# 003_Connectors.net
KiCad netlist of a schematic drawn in Altium Designer
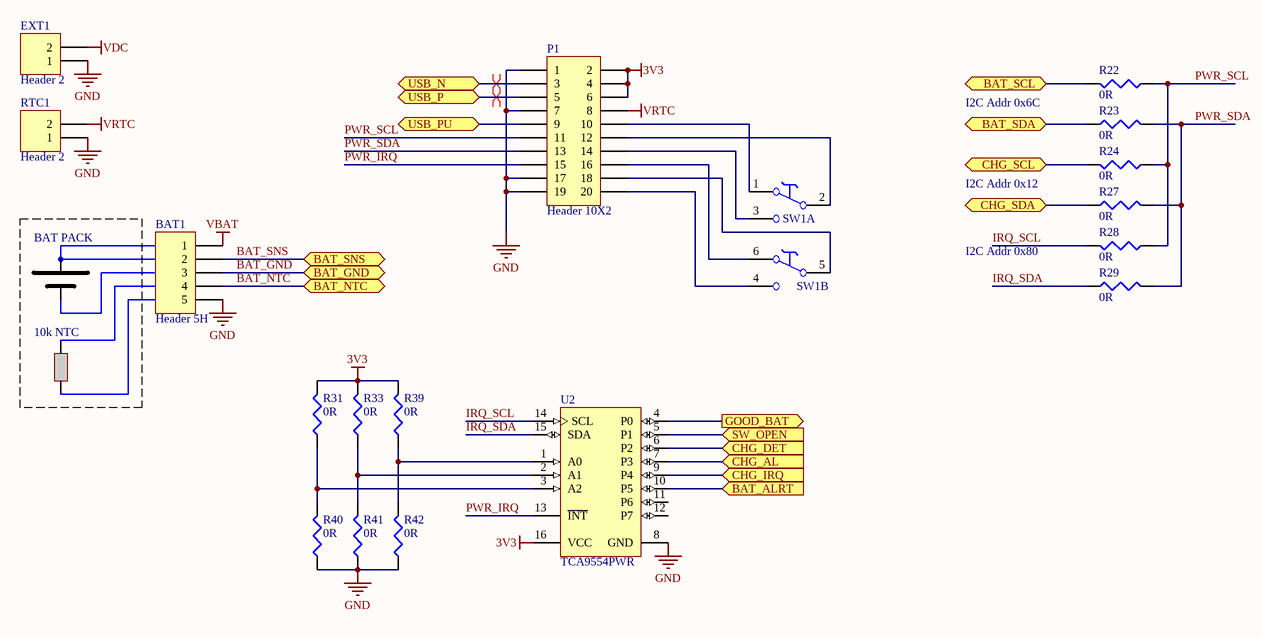
[diagram p0: [003] Connectors.SchDoc]

(export (version "E")
  (design (tool "Eeschema 10.0.6"))
  (components
    (comp (ref "BAT1")
      (value "Header 5H")
      (footprint "MOLEX-705530004")
      (description "Header, 5-Pin, Right Angle")
      (fields (field (name "PUBLISHER") "Altium Limited"))
      (libsource (lib "Miscellaneous Connectors") (part "Header 5H"))
    )
    (comp (ref "EXT1")
      (value "Header 2")
      (footprint "MOLEX-705530001")
      (description "Header, 2-Pin")
      (fields (field (name "PUBLISHER") "Altium Limited"))
      (libsource (lib "Miscellaneous Connectors") (part "Header 2"))
    )
    (comp (ref "P1")
      (value "Header 10X2")
      (footprint "SAMTEC_TSW-110-07-L-D-LL")
      (description "Header, 10-Pin, Dual row")
      (fields (field (name "PUBLISHER") "Altium Limited"))
      (libsource (lib "Miscellaneous Connectors") (part "Header 10X2"))
    )
    (comp (ref "R22")
      (value "0R")
      (footprint "J1-0603")
      (description "Resistor")
      (fields (field (name "Comment") "Res3") (field (name "PUBLISHER") "Altium Limited"))
      (libsource (lib "Miscellaneous Devices") (part "Res3"))
    )
    (comp (ref "R23")
      (value "0R")
      (footprint "J1-0603")
      (description "Resistor")
      (fields (field (name "Comment") "Res3") (field (name "PUBLISHER") "Altium Limited"))
      (libsource (lib "Miscellaneous Devices") (part "Res3"))
    )
    (comp (ref "R24")
      (value "0R")
      (footprint "J1-0603")
      (description "Resistor")
      (fields (field (name "Comment") "Res3") (field (name "PUBLISHER") "Altium Limited"))
      (libsource (lib "Miscellaneous Devices") (part "Res3"))
    )
    (comp (ref "R27")
      (value "0R")
      (footprint "J1-0603")
      (description "Resistor")
      (fields (field (name "Comment") "Res3") (field (name "PUBLISHER") "Altium Limited"))
      (libsource (lib "Miscellaneous Devices") (part "Res3"))
    )
    (comp (ref "R28")
      (value "0R")
      (footprint "J1-0603")
      (description "Resistor")
      (fields (field (name "Comment") "Res3") (field (name "PUBLISHER") "Altium Limited"))
      (libsource (lib "Miscellaneous Devices") (part "Res3"))
    )
    (comp (ref "R29")
      (value "0R")
      (footprint "J1-0603")
      (description "Resistor")
      (fields (field (name "Comment") "Res3") (field (name "PUBLISHER") "Altium Limited"))
      (libsource (lib "Miscellaneous Devices") (part "Res3"))
    )
    (comp (ref "R31")
      (value "0R")
      (footprint "J1-0603")
      (description "Resistor")
      (fields (field (name "Comment") "Res3") (field (name "PUBLISHER") "Altium Limited"))
      (libsource (lib "Miscellaneous Devices") (part "Res3"))
    )
    (comp (ref "R33")
      (value "0R")
      (footprint "J1-0603")
      (description "Resistor")
      (fields (field (name "Comment") "Res3") (field (name "PUBLISHER") "Altium Limited"))
      (libsource (lib "Miscellaneous Devices") (part "Res3"))
    )
    (comp (ref "R39")
      (value "0R")
      (footprint "J1-0603")
      (description "Resistor")
      (fields (field (name "Comment") "Res3") (field (name "PUBLISHER") "Altium Limited"))
      (libsource (lib "Miscellaneous Devices") (part "Res3"))
    )
    (comp (ref "R40")
      (value "0R")
      (footprint "J1-0603")
      (description "Resistor")
      (fields (field (name "Comment") "Res3") (field (name "PUBLISHER") "Altium Limited"))
      (libsource (lib "Miscellaneous Devices") (part "Res3"))
    )
    (comp (ref "R41")
      (value "0R")
      (footprint "J1-0603")
      (description "Resistor")
      (fields (field (name "Comment") "Res3") (field (name "PUBLISHER") "Altium Limited"))
      (libsource (lib "Miscellaneous Devices") (part "Res3"))
    )
    (comp (ref "R42")
      (value "0R")
      (footprint "J1-0603")
      (description "Resistor")
      (fields (field (name "Comment") "Res3") (field (name "PUBLISHER") "Altium Limited"))
      (libsource (lib "Miscellaneous Devices") (part "Res3"))
    )
    (comp (ref "RTC1")
      (value "Header 2")
      (footprint "MOLEX-705530001")
      (description "Header, 2-Pin")
      (fields (field (name "PUBLISHER") "Altium Limited"))
      (libsource (lib "Miscellaneous Connectors") (part "Header 2"))
    )
    (comp (ref "SW1")
      (value "Switch")
      (footprint "EG2215")
      (description "DPDTSwitch")
      (fields
        (field (name "PART NUMBER") "SW_TYCO_1825010-5")
        (field (name "MANUFACTURER") "TYCO")
        (field (name "AUTHOR") "CERN DEM JLC")
      )
      (libsource (lib "Eletro-mechanical") (part "SW DPDT 1NC-2C-3NO-4NO-5C-6NC"))
    )
    (comp (ref "U2")
      (value "TCA9554PWR")
      (footprint "PW16_N")
      (fields (field (name "MANUFACTURER") "Texas Instruments"))
      (libsource (lib "Texas Instruments Interface I2C") (part "TCA9554PWR"))
    )
  )
  (nets
    (net (code "1") (name "/BAT_ALRT") (class "Default")
      (node (ref "U2") (pin "10") (pinfunction "P5_10") (pintype "bidirectional"))
    )
    (net (code "2") (name "/BAT_GND") (class "Default")
      (node (ref "BAT1") (pin "3") (pinfunction "3_3") (pintype "passive"))
    )
    (net (code "3") (name "/BAT_NTC") (class "Default")
      (node (ref "BAT1") (pin "4") (pinfunction "4_4") (pintype "passive"))
    )
    (net (code "4") (name "/BAT_SCL") (class "Default")
      (node (ref "R22") (pin "2") (pinfunction "2_2") (pintype "passive"))
    )
    (net (code "5") (name "/BAT_SDA") (class "Default")
      (node (ref "R23") (pin "1") (pinfunction "1_1") (pintype "passive"))
    )
    (net (code "6") (name "/BAT_SNS") (class "Default")
      (node (ref "BAT1") (pin "2") (pinfunction "2_2") (pintype "passive"))
    )
    (net (code "7") (name "/CHG_AL") (class "Default")
      (node (ref "U2") (pin "7") (pinfunction "P3_7") (pintype "bidirectional"))
    )
    (net (code "8") (name "/CHG_DET") (class "Default")
      (node (ref "U2") (pin "6") (pinfunction "P2_6") (pintype "bidirectional"))
    )
    (net (code "9") (name "/CHG_IRQ") (class "Default")
      (node (ref "U2") (pin "9") (pinfunction "P4_9") (pintype "bidirectional"))
    )
    (net (code "10") (name "/CHG_SCL") (class "Default")
      (node (ref "R24") (pin "2") (pinfunction "2_2") (pintype "passive"))
    )
    (net (code "11") (name "/CHG_SDA") (class "Default")
      (node (ref "R27") (pin "1") (pinfunction "1_1") (pintype "passive"))
    )
    (net (code "12") (name "/GOOD_BAT") (class "Default")
      (node (ref "U2") (pin "4") (pinfunction "P0_4") (pintype "bidirectional"))
    )
    (net (code "13") (name "/IRQ_SCL") (class "Default")
      (node (ref "R28") (pin "2") (pinfunction "2_2") (pintype "passive"))
      (node (ref "U2") (pin "14") (pinfunction "SCL_14") (pintype "input"))
    )
    (net (code "14") (name "/IRQ_SDA") (class "Default")
      (node (ref "R29") (pin "1") (pinfunction "1_1") (pintype "passive"))
      (node (ref "U2") (pin "15") (pinfunction "SDA_15") (pintype "bidirectional"))
    )
    (net (code "15") (name "/PWR_IRQ") (class "Default")
      (node (ref "P1") (pin "15") (pinfunction "15_15") (pintype "passive"))
      (node (ref "U2") (pin "13") (pinfunction "~{INT}_13") (pintype "open_collector"))
    )
    (net (code "16") (name "/PWR_SCL") (class "Default")
      (node (ref "P1") (pin "11") (pinfunction "11_11") (pintype "passive"))
      (node (ref "R22") (pin "1") (pinfunction "1_1") (pintype "passive"))
      (node (ref "R24") (pin "1") (pinfunction "1_1") (pintype "passive"))
      (node (ref "R28") (pin "1") (pinfunction "1_1") (pintype "passive"))
    )
    (net (code "17") (name "/PWR_SDA") (class "Default")
      (node (ref "P1") (pin "13") (pinfunction "13_13") (pintype "passive"))
      (node (ref "R23") (pin "2") (pinfunction "2_2") (pintype "passive"))
      (node (ref "R27") (pin "2") (pinfunction "2_2") (pintype "passive"))
      (node (ref "R29") (pin "2") (pinfunction "2_2") (pintype "passive"))
    )
    (net (code "18") (name "/SW_OPEN") (class "Default")
      (node (ref "U2") (pin "5") (pinfunction "P1_5") (pintype "bidirectional"))
    )
    (net (code "19") (name "/USB_N") (class "Default")
      (node (ref "P1") (pin "3") (pinfunction "3_3") (pintype "passive"))
    )
    (net (code "20") (name "/USB_P") (class "Default")
      (node (ref "P1") (pin "5") (pinfunction "5_5") (pintype "passive"))
    )
    (net (code "21") (name "/USB_PU") (class "Default")
      (node (ref "P1") (pin "9") (pinfunction "9_9") (pintype "passive"))
    )
    (net (code "22") (name "3V3") (class "Default")
      (node (ref "P1") (pin "2") (pinfunction "2_2") (pintype "passive"))
      (node (ref "P1") (pin "4") (pinfunction "4_4") (pintype "passive"))
      (node (ref "P1") (pin "6") (pinfunction "6_6") (pintype "passive"))
      (node (ref "R31") (pin "2") (pinfunction "2_2") (pintype "passive"))
      (node (ref "R33") (pin "2") (pinfunction "2_2") (pintype "passive"))
      (node (ref "R39") (pin "2") (pinfunction "2_2") (pintype "passive"))
      (node (ref "U2") (pin "16") (pinfunction "VCC_16") (pintype "power_in"))
    )
    (net (code "23") (name "GND") (class "Default")
      (node (ref "BAT1") (pin "5") (pinfunction "5_5") (pintype "passive"))
      (node (ref "EXT1") (pin "1") (pinfunction "1_1") (pintype "passive"))
      (node (ref "P1") (pin "1") (pinfunction "1_1") (pintype "passive"))
      (node (ref "P1") (pin "17") (pinfunction "17_17") (pintype "passive"))
      (node (ref "P1") (pin "19") (pinfunction "19_19") (pintype "passive"))
      (node (ref "P1") (pin "7") (pinfunction "7_7") (pintype "passive"))
      (node (ref "R40") (pin "1") (pinfunction "1_1") (pintype "passive"))
      (node (ref "R41") (pin "1") (pinfunction "1_1") (pintype "passive"))
      (node (ref "R42") (pin "1") (pinfunction "1_1") (pintype "passive"))
      (node (ref "RTC1") (pin "1") (pinfunction "1_1") (pintype "passive"))
      (node (ref "U2") (pin "8") (pinfunction "GND_8") (pintype "power_in"))
    )
    (net (code "24") (name "Net-(P1-Pad10)") (class "Default")
      (node (ref "P1") (pin "10") (pinfunction "10_10") (pintype "passive"))
      (node (ref "SW1") (pin "1") (pinfunction "1_1") (pintype "passive"))
    )
    (net (code "25") (name "Net-(P1-Pad12)") (class "Default")
      (node (ref "P1") (pin "12") (pinfunction "12_12") (pintype "passive"))
      (node (ref "SW1") (pin "2") (pinfunction "2_2") (pintype "passive"))
    )
    (net (code "26") (name "Net-(P1-Pad14)") (class "Default")
      (node (ref "P1") (pin "14") (pinfunction "14_14") (pintype "passive"))
      (node (ref "SW1") (pin "3") (pinfunction "3_3") (pintype "passive"))
    )
    (net (code "27") (name "Net-(P1-Pad16)") (class "Default")
      (node (ref "P1") (pin "16") (pinfunction "16_16") (pintype "passive"))
      (node (ref "SW1") (pin "6") (pinfunction "6_6") (pintype "passive"))
    )
    (net (code "28") (name "Net-(P1-Pad18)") (class "Default")
      (node (ref "P1") (pin "18") (pinfunction "18_18") (pintype "passive"))
      (node (ref "SW1") (pin "5") (pinfunction "5_5") (pintype "passive"))
    )
    (net (code "29") (name "Net-(P1-Pad20)") (class "Default")
      (node (ref "P1") (pin "20") (pinfunction "20_20") (pintype "passive"))
      (node (ref "SW1") (pin "4") (pinfunction "4_4") (pintype "passive"))
    )
    (net (code "30") (name "Net-(U2-A0)") (class "Default")
      (node (ref "R39") (pin "1") (pinfunction "1_1") (pintype "passive"))
      (node (ref "R42") (pin "2") (pinfunction "2_2") (pintype "passive"))
      (node (ref "U2") (pin "1") (pinfunction "A0_1") (pintype "input"))
    )
    (net (code "31") (name "Net-(U2-A1)") (class "Default")
      (node (ref "R33") (pin "1") (pinfunction "1_1") (pintype "passive"))
      (node (ref "R41") (pin "2") (pinfunction "2_2") (pintype "passive"))
      (node (ref "U2") (pin "2") (pinfunction "A1_2") (pintype "input"))
    )
    (net (code "32") (name "Net-(U2-A2)") (class "Default")
      (node (ref "R31") (pin "1") (pinfunction "1_1") (pintype "passive"))
      (node (ref "R40") (pin "2") (pinfunction "2_2") (pintype "passive"))
      (node (ref "U2") (pin "3") (pinfunction "A2_3") (pintype "input"))
    )
    (net (code "33") (name "VBAT") (class "Default")
      (node (ref "BAT1") (pin "1") (pinfunction "1_1") (pintype "passive"))
    )
    (net (code "34") (name "VDC") (class "Default")
      (node (ref "EXT1") (pin "2") (pinfunction "2_2") (pintype "passive"))
    )
    (net (code "35") (name "VRTC") (class "Default")
      (node (ref "P1") (pin "8") (pinfunction "8_8") (pintype "passive"))
      (node (ref "RTC1") (pin "2") (pinfunction "2_2") (pintype "passive"))
    )
    (net (code "36") (name "unconnected-(U2-P6-Pad11)") (class "Default")
      (node (ref "U2") (pin "11") (pinfunction "P6_11") (pintype "bidirectional"))
    )
    (net (code "37") (name "unconnected-(U2-P7-Pad12)") (class "Default")
      (node (ref "U2") (pin "12") (pinfunction "P7_12") (pintype "bidirectional"))
    )
  )
)
